# Monitor_Blanking_V3.net
KiCad netlist of a schematic drawn in Altium Designer
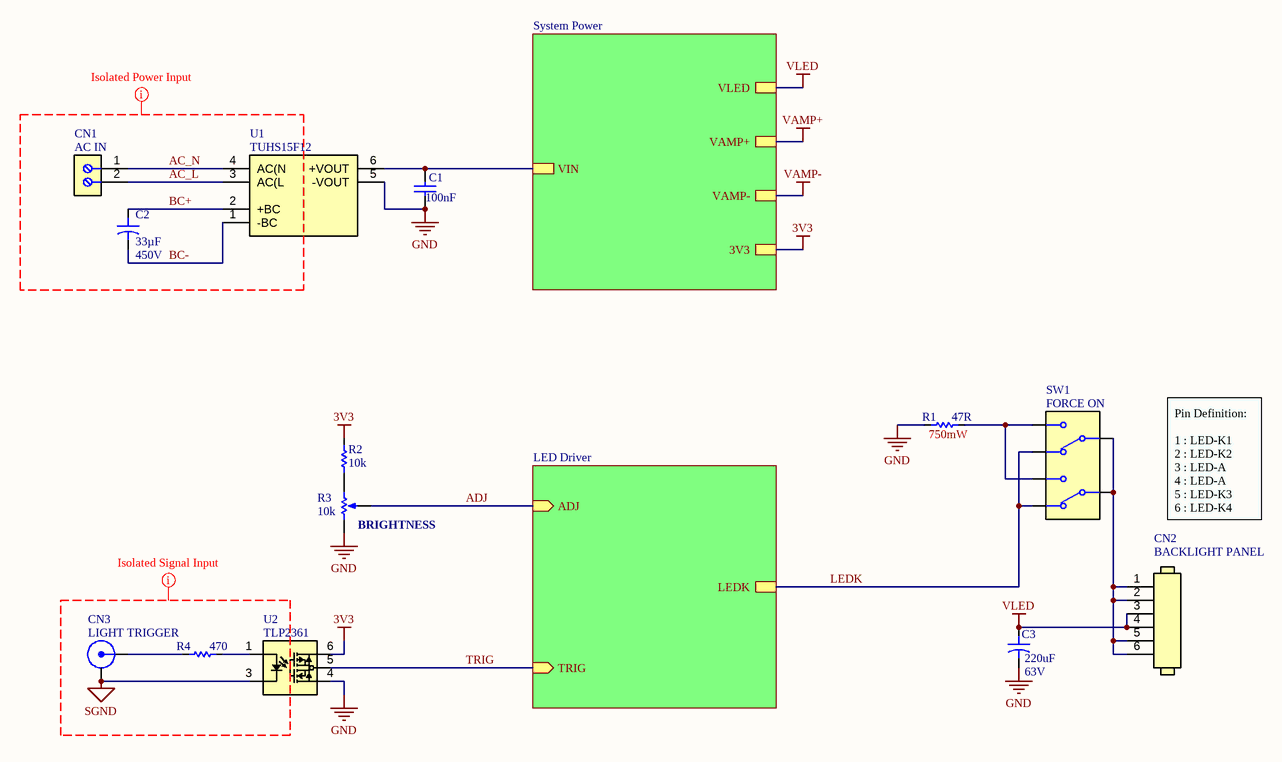
[diagram p0: Monitor Blanking V3.SchDoc]

(export (version "E")
  (design (tool "Eeschema 10.0.6"))
  (components
    (comp (ref "C1")
      (value "100nF")
      (footprint "CAP_CHIP_0603")
      (description "0603 Multilayer Ceramic Capacitors MLCC")
      (fields (field (name "TOLERANCE") "10%") (field (name "PARTNUMBER") "CC0603KRX7R9BB104"))
      (libsource (lib "Sainsbury Wellcome Centre") (part "Cap"))
    )
    (comp (ref "C2")
      (value "33µF")
      (footprint "ECAP_DIP_12.5_90")
      (fields
        (field (name "TOLERANCE") "20%")
        (field (name "VOLTAGE RATING") "450V")
        (field (name "PARTNUMBER") "450BXW33MEFR12.5X25")
        (field (name "Comment") "EC125-33uF-450V")
      )
      (libsource (lib "Sainsbury Wellcome Centre") (part "Cap Pol 2"))
    )
    (comp (ref "C3")
      (value "220uF")
      (footprint "ECAP_SMD_D12.5_13.5L")
      (description "Radial Can - SMD ALUMINUM ELECTROLYTIC CAPACITOR FK 63V 220muF 20% 0.492Dia 12.50mm")
      (fields
        (field (name "PARTNUMBER") "EEEFK1J221AQ")
        (field (name "VOLTAGE RATING") "63V")
        (field (name "TOLERANCE") "20%")
      )
      (libsource (lib "Sainsbury Wellcome Centre") (part "Cap Pol 2"))
    )
    (comp (ref "CN1")
      (value "AC IN")
      (footprint "BT-8.26-1X2P")
      (description "CONN BARRIER STRIP 2CIRC 0.325\"")
      (fields (field (name "PARTNUMBER") "4DB-P108-02"))
      (libsource (lib "Sainsbury Wellcome Centre") (part "Terminal Block 2"))
    )
    (comp (ref "CN2")
      (value "BACKLIGHT PANEL")
      (footprint "PH_DIP_90_1X6P")
      (description "Wire-To-Board Connector, Right Angle, 2 mm, 2 Contacts, Header, PH Series")
      (fields (field (name "PARTNUMBER") "X2016WR-06-46SN"))
      (libsource (lib "Sainsbury Wellcome Centre") (part "Wire to Board 1x6"))
    )
    (comp (ref "CN3")
      (value "LIGHT TRIGGER")
      (footprint "BNC-TE-5227222")
      (description "RF BNC Connector, Female, Panel Mount, Board Mount, Solder Terminal, Jack")
      (fields (field (name "PARTNUMBER") "5227222-3"))
      (libsource (lib "Sainsbury Wellcome Centre") (part "RF-Jack"))
    )
    (comp (ref "R1")
      (value "47R")
      (footprint "RES_CHIP_2010")
      (description "Res Thick Film 2010 47 Ohm 1% 3/4W ±100ppm/°C Molded SMD SMD Embossed T/R")
      (fields
        (field (name "TOLERANCE") "1%")
        (field (name "POWER RATING") "750mW")
        (field (name "PARTNUMBER") "RC2010FK-0747RL")
      )
      (libsource (lib "Sainsbury Wellcome Centre") (part "Res"))
    )
    (comp (ref "R2")
      (value "10k")
      (footprint "RES_CHIP_0603")
      (description "100mW Thick Film Resistors 75V ±100ppm/℃ ±1% 0603 Chip Resistor")
      (fields (field (name "PARTNUMBER") "0603WAF1002T5E") (field (name "TOLERANCE") "1%"))
      (libsource (lib "Sainsbury Wellcome Centre") (part "Res"))
    )
    (comp (ref "R3")
      (value "BRIGHTNESS")
      (footprint "RK09L1140")
      (description "Potentiometer, 0.05W, 10000ohm, 10V, 20% +/-Tol, 1 Turn(s), 4845")
      (fields
        (field (name "TOLERANCE") "20%")
        (field (name "ALTIUM_VALUE") "10k")
        (field (name "PARTNUMBER") "RK09L114001T")
      )
      (libsource (lib "Sainsbury Wellcome Centre") (part "Pot-W2"))
    )
    (comp (ref "R4")
      (value "470")
      (footprint "RES_CHIP_0603")
      (description "100mW Thick Film Resistors 75V ±100ppm/℃ ±1% 0603 Chip Resistor")
      (fields (field (name "PARTNUMBER") "0603WAF4700T5E") (field (name "TOLERANCE") "1%"))
      (libsource (lib "Sainsbury Wellcome Centre") (part "Res"))
    )
    (comp (ref "SW1")
      (value "FORCE ON")
      (footprint "SW_LOCK_SPPH410100")
      (description "Switch Push Button N.O./N.C. DPDT Plunger 0.1A 30VDC Latching PC Pins Thru-Hole Bulk")
      (fields (field (name "PARTNUMBER") "SPPH410100"))
      (libsource (lib "Sainsbury Wellcome Centre") (part "DPDT"))
    )
    (comp (ref "U1")
      (value "TUHS15F12")
      (footprint "TUHS15F12")
      (description "AC/DC 15W 12V Single Output Power Supply, Encapsulated Board Mount Module")
      (fields (field (name "PARTNUMBER") "TUHS15F12"))
      (libsource (lib "Sainsbury Wellcome Centre") (part "TUHS15F12"))
    )
    (comp (ref "U2")
      (value "TLP2361")
      (footprint "SO5")
      (description "Logic IC Output Optocoupler, 1-Channel, 1-Element, 3750V Isolation, 20MBps")
      (fields (field (name "PARTNUMBER") "TLP2361(TPL,E(T"))
      (libsource (lib "Sainsbury Wellcome Centre") (part "Logic Output Optoisolator"))
    )
  )
  (nets
    (net (code "1") (name "/AC_L") (class "Default")
      (node (ref "CN1") (pin "2") (pinfunction "2_2") (pintype "passive"))
      (node (ref "U1") (pin "3") (pinfunction "AC(L_3") (pintype "power_in"))
    )
    (net (code "2") (name "/AC_N") (class "Default")
      (node (ref "CN1") (pin "1") (pinfunction "1_1") (pintype "passive"))
      (node (ref "U1") (pin "4") (pinfunction "AC(N_4") (pintype "power_in"))
    )
    (net (code "3") (name "/ADJ") (class "Default")
      (node (ref "R3") (pin "2") (pinfunction "TAP_2") (pintype "passive"))
    )
    (net (code "4") (name "/BC+") (class "Default")
      (node (ref "C2") (pin "1") (pinfunction "1_1") (pintype "passive"))
      (node (ref "U1") (pin "2") (pinfunction "+BC_2") (pintype "power_in"))
    )
    (net (code "5") (name "/BC-") (class "Default")
      (node (ref "C2") (pin "2") (pinfunction "2_2") (pintype "passive"))
      (node (ref "U1") (pin "1") (pinfunction "-BC_1") (pintype "power_in"))
    )
    (net (code "6") (name "/LEDK") (class "Default")
      (node (ref "SW1") (pin "1") (pinfunction "NCA_1") (pintype "passive"))
      (node (ref "SW1") (pin "4") (pinfunction "NCB_4") (pintype "passive"))
    )
    (net (code "7") (name "/TRIG") (class "Default")
      (node (ref "U2") (pin "5") (pinfunction "Vo_5") (pintype "passive"))
    )
    (net (code "8") (name "/VIN") (class "Default")
      (node (ref "C1") (pin "2") (pinfunction "2_2") (pintype "passive"))
      (node (ref "U1") (pin "6") (pinfunction "+VOUT_6") (pintype "power_in"))
    )
    (net (code "9") (name "3V3") (class "Default")
      (node (ref "R2") (pin "2") (pinfunction "2_2") (pintype "passive"))
      (node (ref "U2") (pin "6") (pinfunction "VCC_6") (pintype "passive"))
    )
    (net (code "10") (name "GND") (class "Default")
      (node (ref "C1") (pin "1") (pinfunction "1_1") (pintype "passive"))
      (node (ref "C3") (pin "2") (pinfunction "2_2") (pintype "passive"))
      (node (ref "R1") (pin "1") (pinfunction "1_1") (pintype "passive"))
      (node (ref "R3") (pin "1") (pinfunction "TOP_1") (pintype "passive"))
      (node (ref "U1") (pin "5") (pinfunction "-VOUT_5") (pintype "power_in"))
      (node (ref "U2") (pin "4") (pinfunction "GND_4") (pintype "passive"))
    )
    (net (code "11") (name "Net-(CN2-d)") (class "Default")
      (node (ref "CN2") (pin "1") (pinfunction "d_1") (pintype "passive"))
      (node (ref "CN2") (pin "2") (pinfunction "2_2") (pintype "passive"))
      (node (ref "CN2") (pin "5") (pinfunction "5_5") (pintype "passive"))
      (node (ref "CN2") (pin "6") (pinfunction "6_6") (pintype "passive"))
      (node (ref "SW1") (pin "2") (pinfunction "COMA_2") (pintype "passive"))
      (node (ref "SW1") (pin "5") (pinfunction "COMB_5") (pintype "passive"))
    )
    (net (code "12") (name "Net-(CN3-SIG)") (class "Default")
      (node (ref "CN3") (pin "1") (pinfunction "SIG_1") (pintype "passive"))
      (node (ref "R4") (pin "1") (pinfunction "1_1") (pintype "passive"))
    )
    (net (code "13") (name "Net-(R3-BOT)") (class "Default")
      (node (ref "R2") (pin "1") (pinfunction "1_1") (pintype "passive"))
      (node (ref "R3") (pin "3") (pinfunction "BOT_3") (pintype "passive"))
    )
    (net (code "14") (name "Net-(SW1-NOA)") (class "Default")
      (node (ref "R1") (pin "2") (pinfunction "2_2") (pintype "passive"))
      (node (ref "SW1") (pin "3") (pinfunction "NOA_3") (pintype "passive"))
      (node (ref "SW1") (pin "6") (pinfunction "NOB_6") (pintype "passive"))
    )
    (net (code "15") (name "Net-(U2-Anode)") (class "Default")
      (node (ref "R4") (pin "2") (pinfunction "2_2") (pintype "passive"))
      (node (ref "U2") (pin "1") (pinfunction "Anode_1") (pintype "passive"))
    )
    (net (code "16") (name "SGND") (class "Default")
      (node (ref "CN3") (pin "2") (pinfunction "GND_2") (pintype "passive"))
      (node (ref "U2") (pin "3") (pinfunction "Cathode_3") (pintype "passive"))
    )
    (net (code "19") (name "VLED") (class "Default")
      (node (ref "C3") (pin "1") (pinfunction "1_1") (pintype "passive"))
      (node (ref "CN2") (pin "3") (pinfunction "3_3") (pintype "passive"))
      (node (ref "CN2") (pin "4") (pinfunction "4_4") (pintype "passive"))
    )
  )
)
